# piezo-preamp-tickler_V2-RevA.net
KiCad netlist of a schematic drawn in EAGLE
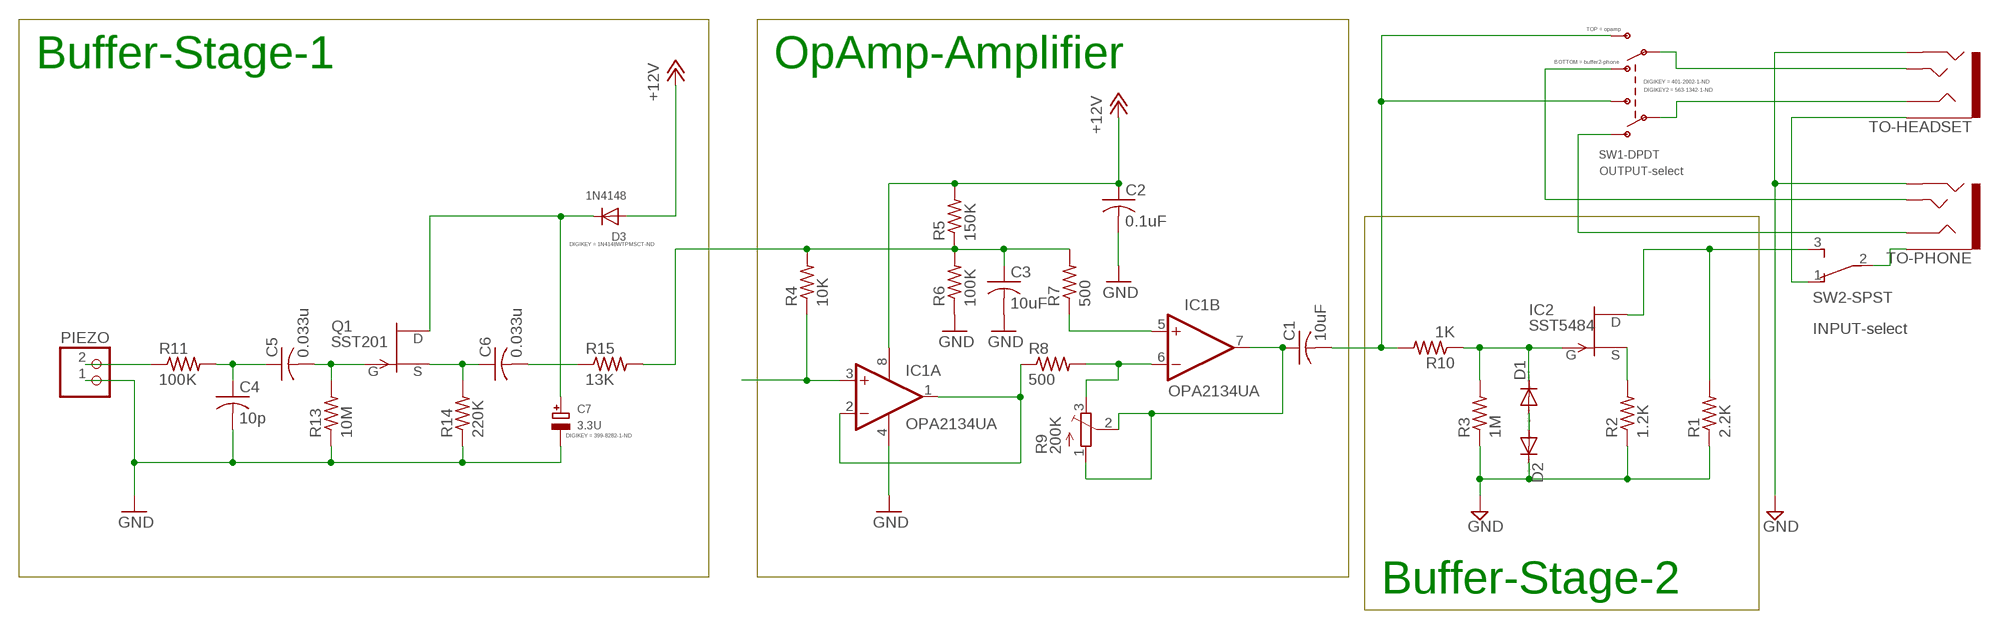
[diagram p0: schematic, sheet 1]
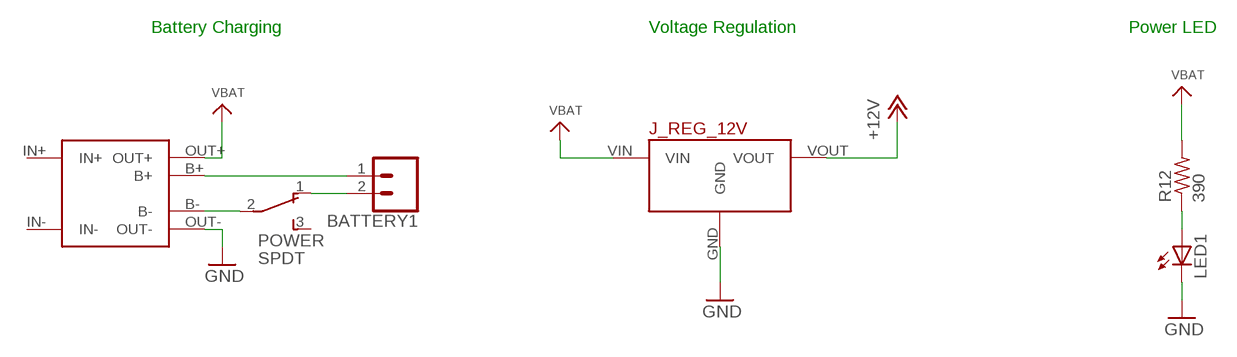
[diagram p1: schematic, sheet 2]

(export (version "E")
  (design (tool "Eeschema 10.0.6"))
  (components
    (comp (ref "C1")
      (value "10uF")
      (footprint "eagle-import:C0805K")
      (libsource (lib "eagle-import") (part "C-USC0805K"))
    )
    (comp (ref "C2")
      (value "0.1uF")
      (footprint "eagle-import:C0805K")
      (libsource (lib "eagle-import") (part "C-USC0805K"))
    )
    (comp (ref "C3")
      (value "10uF")
      (footprint "eagle-import:C0805K")
      (libsource (lib "eagle-import") (part "C-USC0805K"))
    )
    (comp (ref "C4")
      (value "10p")
      (footprint "eagle-import:C0805K")
      (libsource (lib "eagle-import") (part "C-USC0805K"))
    )
    (comp (ref "C5")
      (value "0.033u")
      (footprint "eagle-import:C0805K")
      (libsource (lib "eagle-import") (part "C-USC0805K"))
    )
    (comp (ref "C6")
      (value "0.033u")
      (footprint "eagle-import:C0805K")
      (libsource (lib "eagle-import") (part "C-USC0805K"))
    )
    (comp (ref "C7")
      (value "3.3U")
      (footprint "eagle-import:EIA3216-18_A-R")
      (fields (field (name "DIGIKEY") "399-8282-1-ND"))
      (libsource (lib "eagle-import") (part "CAP_TANTALUMA/3216_REFLOW"))
    )
    (comp (ref "D1")
      (value "DIODE-SOD123")
      (footprint "eagle-import:SOD123")
      (libsource (lib "eagle-import") (part "DIODE-SOD123"))
    )
    (comp (ref "D2")
      (value "DIODE-SOD123")
      (footprint "eagle-import:SOD123")
      (libsource (lib "eagle-import") (part "DIODE-SOD123"))
    )
    (comp (ref "D3")
      (value "1N4148")
      (footprint "eagle-import:SOD-123")
      (fields (field (name "DIGIKEY") "1N4148WTPMSCT-ND"))
      (libsource (lib "eagle-import") (part "DIODESOD-123"))
    )
    (comp (ref "IC1")
      (value "OPA2134UA")
      (footprint "eagle-import:SO08")
      (libsource (lib "eagle-import") (part "OPA2UA134"))
    )
    (comp (ref "IC2")
      (value "SST5484")
      (footprint "eagle-import:SOT23")
      (libsource (lib "eagle-import") (part "?548SST4"))
    )
    (comp (ref "PIEZO")
      (value "JST_2PIN-THM")
      (footprint "eagle-import:JST-PH-2-THM")
      (libsource (lib "eagle-import") (part "JST_2PIN-THM"))
    )
    (comp (ref "Q1")
      (value "SST201")
      (footprint "eagle-import:SOT23")
      (libsource (lib "eagle-import") (part "?20SST1"))
    )
    (comp (ref "R1")
      (value "2.2K")
      (footprint "eagle-import:R0603")
      (libsource (lib "eagle-import") (part "R-US_R0603"))
    )
    (comp (ref "R2")
      (value "1.2K")
      (footprint "eagle-import:R0603")
      (libsource (lib "eagle-import") (part "R-US_R0603"))
    )
    (comp (ref "R3")
      (value "1M")
      (footprint "eagle-import:R0603")
      (libsource (lib "eagle-import") (part "R-US_R0603"))
    )
    (comp (ref "R4")
      (value "10K")
      (footprint "eagle-import:R0603")
      (libsource (lib "eagle-import") (part "R-US_R0603"))
    )
    (comp (ref "R5")
      (value "150K")
      (footprint "eagle-import:R0603")
      (libsource (lib "eagle-import") (part "R-US_R0603"))
    )
    (comp (ref "R6")
      (value "100K")
      (footprint "eagle-import:R0603")
      (libsource (lib "eagle-import") (part "R-US_R0603"))
    )
    (comp (ref "R7")
      (value "500")
      (footprint "eagle-import:R0603")
      (libsource (lib "eagle-import") (part "R-US_R0603"))
    )
    (comp (ref "R8")
      (value "500")
      (footprint "eagle-import:R0603")
      (libsource (lib "eagle-import") (part "R-US_R0603"))
    )
    (comp (ref "R9")
      (value "200K")
      (footprint "eagle-import:TC33X")
      (libsource (lib "eagle-import") (part "TRIMPOTTC33X"))
    )
    (comp (ref "R10")
      (value "1K")
      (footprint "eagle-import:R0603")
      (libsource (lib "eagle-import") (part "R-US_R0603"))
    )
    (comp (ref "R11")
      (value "100K")
      (footprint "eagle-import:R0603")
      (libsource (lib "eagle-import") (part "R-US_R0603"))
    )
    (comp (ref "R13")
      (value "10M")
      (footprint "eagle-import:R0603")
      (libsource (lib "eagle-import") (part "R-US_R0603"))
    )
    (comp (ref "R14")
      (value "220K")
      (footprint "eagle-import:R0603")
      (libsource (lib "eagle-import") (part "R-US_R0603"))
    )
    (comp (ref "R15")
      (value "13K")
      (footprint "eagle-import:R0603")
      (libsource (lib "eagle-import") (part "R-US_R0603"))
    )
    (comp (ref "SW1-DPDT")
      (value "OUTPUT-select")
      (footprint "eagle-import:DPDT_SMT_JS202011SCQN")
      (fields
        (field (name "BOTTOM") "buffer2-phone")
        (field (name "DIGIKEY") "401-2002-1-ND")
        (field (name "DIGIKEY2") "563-1342-1-ND")
        (field (name "TOP") "opamp")
      )
      (libsource (lib "eagle-import") (part "SWITCH_DPDT"))
    )
    (comp (ref "SW2-SPST")
      (value "INPUT-select")
      (footprint "eagle-import:SWITCH_SPDT-TE-CONNECT")
      (libsource (lib "eagle-import") (part "SWITCH_SPDTTE-CONNECT"))
    )
    (comp (ref "TO-HEADSET")
      (value "AUDIO-JACK3LGPADS")
      (footprint "eagle-import:AUDIO-JACK-TRRS-SMD")
      (libsource (lib "eagle-import") (part "AUDIO-JACK3LGPADS"))
    )
    (comp (ref "TO-PHONE")
      (value "AUDIO-JACK3LGPADS")
      (footprint "eagle-import:AUDIO-JACK-TRRS-SMD")
      (libsource (lib "eagle-import") (part "AUDIO-JACK3LGPADS"))
    )
    (comp (ref "BATTERY1")
      (value "CONN_02LOCK")
      (footprint "eagle-import:1X02_LOCK")
      (libsource (lib "eagle-import") (part "CONN_02LOCK"))
    )
    (comp (ref "J_REG_12V")
      (value "POLOLU_VOLTAGE_REGULATORS_3PIN")
      (footprint "eagle-import:POLOLU_5V-12V_STEPUP_U3V12F5-U3V12F12")
      (libsource (lib "eagle-import") (part "POLOLU_VOLTAGE_REGULATORS_3PIN"))
    )
    (comp (ref "LED1")
      (value "LED3MM")
      (footprint "eagle-import:LED3MM")
      (libsource (lib "eagle-import") (part "LED3MM"))
    )
    (comp (ref "POWER")
      (value "SPDT")
      (footprint "eagle-import:SWITCH_SPDT-TE-CONNECT")
      (libsource (lib "eagle-import") (part "SWITCH_SPDTTE-CONNECT"))
    )
    (comp (ref "R12")
      (value "390")
      (footprint "eagle-import:R0805")
      (libsource (lib "eagle-import") (part "R-US_R0805"))
    )
    (comp (ref "USB-LIPO-CHARGER")
      (value "TP4056-MODULE")
      (footprint "eagle-import:TP4056-LITHIUM-PROTECTED-MODULE")
      (libsource (lib "eagle-import") (part "TP4056-MODULE"))
    )
  )
  (nets
    (net (code "1") (name "+12V") (class "Default")
      (node (ref "C2") (pin "1") (pinfunction "1_1") (pintype "passive"))
      (node (ref "D3") (pin "A") (pinfunction "A_A") (pintype "passive"))
      (node (ref "IC1") (pin "8") (pinfunction "V+_8") (pintype "power_in"))
      (node (ref "J_REG_12V") (pin "VOUT") (pinfunction "VOUT_VOUT") (pintype "bidirectional"))
      (node (ref "R5") (pin "2") (pinfunction "2_2") (pintype "passive"))
    )
    (net (code "2") (name "GND") (class "Default")
      (node (ref "C2") (pin "2") (pinfunction "2_2") (pintype "passive"))
      (node (ref "C3") (pin "2") (pinfunction "2_2") (pintype "passive"))
      (node (ref "C4") (pin "2") (pinfunction "2_2") (pintype "passive"))
      (node (ref "C7") (pin "-") (pinfunction "-_-") (pintype "passive"))
      (node (ref "D2") (pin "C") (pinfunction "C_C") (pintype "passive"))
      (node (ref "IC1") (pin "4") (pinfunction "V-_4") (pintype "power_in"))
      (node (ref "J_REG_12V") (pin "GND") (pinfunction "GND_GND") (pintype "bidirectional"))
      (node (ref "LED1") (pin "K") (pinfunction "C_K") (pintype "passive"))
      (node (ref "PIEZO") (pin "1") (pinfunction "2_1") (pintype "passive"))
      (node (ref "R1") (pin "1") (pinfunction "1_1") (pintype "passive"))
      (node (ref "R13") (pin "1") (pinfunction "1_1") (pintype "passive"))
      (node (ref "R14") (pin "1") (pinfunction "1_1") (pintype "passive"))
      (node (ref "R2") (pin "1") (pinfunction "1_1") (pintype "passive"))
      (node (ref "R3") (pin "1") (pinfunction "1_1") (pintype "passive"))
      (node (ref "R6") (pin "1") (pinfunction "1_1") (pintype "passive"))
      (node (ref "TO-HEADSET") (pin "RING2") (pinfunction "RING2_RING2") (pintype "bidirectional"))
      (node (ref "TO-PHONE") (pin "RING2") (pinfunction "RING2_RING2") (pintype "bidirectional"))
      (node (ref "USB-LIPO-CHARGER") (pin "OUT-") (pinfunction "OUT-_OUT-") (pintype "power_in"))
    )
    (net (code "3") (name "IN+") (class "Default")
      (node (ref "USB-LIPO-CHARGER") (pin "IN+") (pinfunction "IN+_IN+") (pintype "power_in"))
    )
    (net (code "4") (name "IN-") (class "Default")
      (node (ref "USB-LIPO-CHARGER") (pin "IN-") (pinfunction "IN-_IN-") (pintype "power_in"))
    )
    (net (code "5") (name "Net-(BATTERY1-Pad1)") (class "Default")
      (node (ref "BATTERY1") (pin "1") (pinfunction "1_1") (pintype "passive"))
      (node (ref "USB-LIPO-CHARGER") (pin "B+") (pinfunction "B+_B+") (pintype "power_in"))
    )
    (net (code "6") (name "Net-(BATTERY1-Pad2)") (class "Default")
      (node (ref "BATTERY1") (pin "2") (pinfunction "2_2") (pintype "passive"))
      (node (ref "POWER") (pin "1") (pinfunction "1_1") (pintype "passive"))
    )
    (net (code "7") (name "Net-(C3-Pad1)") (class "Default")
      (node (ref "C3") (pin "1") (pinfunction "1_1") (pintype "passive"))
      (node (ref "R15") (pin "2") (pinfunction "2_2") (pintype "passive"))
      (node (ref "R4") (pin "2") (pinfunction "2_2") (pintype "passive"))
      (node (ref "R5") (pin "1") (pinfunction "1_1") (pintype "passive"))
      (node (ref "R6") (pin "2") (pinfunction "2_2") (pintype "passive"))
      (node (ref "R7") (pin "2") (pinfunction "2_2") (pintype "passive"))
    )
    (net (code "8") (name "Net-(C4-Pad1)") (class "Default")
      (node (ref "C4") (pin "1") (pinfunction "1_1") (pintype "passive"))
      (node (ref "C5") (pin "1") (pinfunction "1_1") (pintype "passive"))
      (node (ref "R11") (pin "2") (pinfunction "2_2") (pintype "passive"))
    )
    (net (code "9") (name "Net-(C6-Pad2)") (class "Default")
      (node (ref "C6") (pin "2") (pinfunction "2_2") (pintype "passive"))
      (node (ref "R15") (pin "1") (pinfunction "1_1") (pintype "passive"))
    )
    (net (code "10") (name "Net-(D1-PadA)") (class "Default")
      (node (ref "D1") (pin "A") (pinfunction "A_A") (pintype "passive"))
      (node (ref "D2") (pin "A") (pinfunction "A_A") (pintype "passive"))
    )
    (net (code "11") (name "Net-(IC1A-+IN)") (class "Default")
      (node (ref "IC1") (pin "3") (pinfunction "+IN_3") (pintype "input"))
      (node (ref "R4") (pin "1") (pinfunction "1_1") (pintype "passive"))
    )
    (net (code "12") (name "Net-(IC1A--IN)") (class "Default")
      (node (ref "IC1") (pin "1") (pinfunction "OUT_1") (pintype "output"))
      (node (ref "IC1") (pin "2") (pinfunction "-IN_2") (pintype "input"))
      (node (ref "R8") (pin "1") (pinfunction "1_1") (pintype "passive"))
    )
    (net (code "13") (name "Net-(IC1B-+IN)") (class "Default")
      (node (ref "IC1") (pin "5") (pinfunction "+IN_5") (pintype "input"))
      (node (ref "R7") (pin "1") (pinfunction "1_1") (pintype "passive"))
    )
    (net (code "14") (name "Net-(IC1B--IN)") (class "Default")
      (node (ref "IC1") (pin "6") (pinfunction "-IN_6") (pintype "input"))
      (node (ref "R8") (pin "2") (pinfunction "2_2") (pintype "passive"))
      (node (ref "R9") (pin "3") (pinfunction "E_3") (pintype "passive"))
    )
    (net (code "15") (name "Net-(IC1B-OUT)") (class "Default")
      (node (ref "C1") (pin "1") (pinfunction "1_1") (pintype "passive"))
      (node (ref "IC1") (pin "7") (pinfunction "OUT_7") (pintype "output"))
      (node (ref "R9") (pin "1") (pinfunction "A_1") (pintype "passive"))
      (node (ref "R9") (pin "2") (pinfunction "S_2") (pintype "passive"))
    )
    (net (code "16") (name "Net-(IC2-D)") (class "Default")
      (node (ref "IC2") (pin "1") (pinfunction "D_1") (pintype "passive"))
      (node (ref "R1") (pin "2") (pinfunction "2_2") (pintype "passive"))
      (node (ref "SW2-SPST") (pin "3") (pinfunction "3_3") (pintype "passive"))
    )
    (net (code "17") (name "Net-(IC2-G)") (class "Default")
      (node (ref "D1") (pin "C") (pinfunction "C_C") (pintype "passive"))
      (node (ref "IC2") (pin "3") (pinfunction "G_3") (pintype "passive"))
      (node (ref "R10") (pin "1") (pinfunction "1_1") (pintype "passive"))
      (node (ref "R3") (pin "2") (pinfunction "2_2") (pintype "passive"))
    )
    (net (code "18") (name "Net-(IC2-S)") (class "Default")
      (node (ref "IC2") (pin "2") (pinfunction "S_2") (pintype "passive"))
      (node (ref "R2") (pin "2") (pinfunction "2_2") (pintype "passive"))
    )
    (net (code "19") (name "Net-(LED1-PadA)") (class "Default")
      (node (ref "LED1") (pin "A") (pinfunction "A_A") (pintype "passive"))
      (node (ref "R12") (pin "1") (pinfunction "1_1") (pintype "passive"))
    )
    (net (code "20") (name "Net-(PIEZO-1)") (class "Default")
      (node (ref "PIEZO") (pin "2") (pinfunction "1_2") (pintype "passive"))
      (node (ref "R11") (pin "1") (pinfunction "1_1") (pintype "passive"))
    )
    (net (code "21") (name "Net-(POWER-Pad2)") (class "Default")
      (node (ref "POWER") (pin "2") (pinfunction "2_2") (pintype "passive"))
      (node (ref "USB-LIPO-CHARGER") (pin "B-") (pinfunction "B-_B-") (pintype "power_in"))
    )
    (net (code "22") (name "Net-(Q1-D)") (class "Default")
      (node (ref "C7") (pin "+") (pinfunction "+_+") (pintype "passive"))
      (node (ref "D3") (pin "C") (pinfunction "C_C") (pintype "passive"))
      (node (ref "Q1") (pin "1") (pinfunction "D_1") (pintype "passive"))
    )
    (net (code "23") (name "Net-(Q1-G)") (class "Default")
      (node (ref "C5") (pin "2") (pinfunction "2_2") (pintype "passive"))
      (node (ref "Q1") (pin "3") (pinfunction "G_3") (pintype "passive"))
      (node (ref "R13") (pin "2") (pinfunction "2_2") (pintype "passive"))
    )
    (net (code "24") (name "Net-(Q1-S)") (class "Default")
      (node (ref "C6") (pin "1") (pinfunction "1_1") (pintype "passive"))
      (node (ref "Q1") (pin "2") (pinfunction "S_2") (pintype "passive"))
      (node (ref "R14") (pin "2") (pinfunction "2_2") (pintype "passive"))
    )
    (net (code "25") (name "Net-(SW1-DPDT-O1)") (class "Default")
      (node (ref "SW1-DPDT") (pin "P$1") (pinfunction "O1_P$1") (pintype "passive"))
      (node (ref "TO-PHONE") (pin "RING1") (pinfunction "RING1_RING1") (pintype "bidirectional"))
    )
    (net (code "26") (name "Net-(SW1-DPDT-O2)") (class "Default")
      (node (ref "SW1-DPDT") (pin "P$6") (pinfunction "O2_P$6") (pintype "passive"))
      (node (ref "TO-PHONE") (pin "TIP") (pinfunction "TIP_TIP") (pintype "bidirectional"))
    )
    (net (code "27") (name "Net-(SW1-DPDT-P1)") (class "Default")
      (node (ref "SW1-DPDT") (pin "P$2") (pinfunction "P1_P$2") (pintype "passive"))
      (node (ref "TO-HEADSET") (pin "RING1") (pinfunction "RING1_RING1") (pintype "bidirectional"))
    )
    (net (code "28") (name "Net-(SW1-DPDT-P2)") (class "Default")
      (node (ref "SW1-DPDT") (pin "P$5") (pinfunction "P2_P$5") (pintype "passive"))
      (node (ref "TO-HEADSET") (pin "TIP") (pinfunction "TIP_TIP") (pintype "bidirectional"))
    )
    (net (code "29") (name "Net-(SW1-DPDT-S1)") (class "Default")
      (node (ref "C1") (pin "2") (pinfunction "2_2") (pintype "passive"))
      (node (ref "R10") (pin "2") (pinfunction "2_2") (pintype "passive"))
      (node (ref "SW1-DPDT") (pin "P$3") (pinfunction "S1_P$3") (pintype "passive"))
      (node (ref "SW1-DPDT") (pin "P$4") (pinfunction "S2_P$4") (pintype "passive"))
    )
    (net (code "30") (name "Net-(SW2-SPST-Pad1)") (class "Default")
      (node (ref "SW2-SPST") (pin "1") (pinfunction "1_1") (pintype "passive"))
      (node (ref "TO-HEADSET") (pin "EARTH") (pinfunction "EARTH_EARTH") (pintype "bidirectional"))
    )
    (net (code "31") (name "Net-(SW2-SPST-Pad2)") (class "Default")
      (node (ref "SW2-SPST") (pin "2") (pinfunction "2_2") (pintype "passive"))
      (node (ref "TO-PHONE") (pin "EARTH") (pinfunction "EARTH_EARTH") (pintype "bidirectional"))
    )
    (net (code "32") (name "VBAT") (class "Default")
      (node (ref "J_REG_12V") (pin "VIN") (pinfunction "VIN_VIN") (pintype "bidirectional"))
      (node (ref "R12") (pin "2") (pinfunction "2_2") (pintype "passive"))
      (node (ref "USB-LIPO-CHARGER") (pin "OUT+") (pinfunction "OUT+_OUT+") (pintype "power_in"))
    )
    (net (code "33") (name "unconnected-(POWER-Pad3)") (class "Default")
      (node (ref "POWER") (pin "3") (pinfunction "3_3") (pintype "passive"))
    )
  )
)
